# UpperPlumbingBayBoardSchematic.net
KiCad netlist of a schematic drawn in Altium Designer
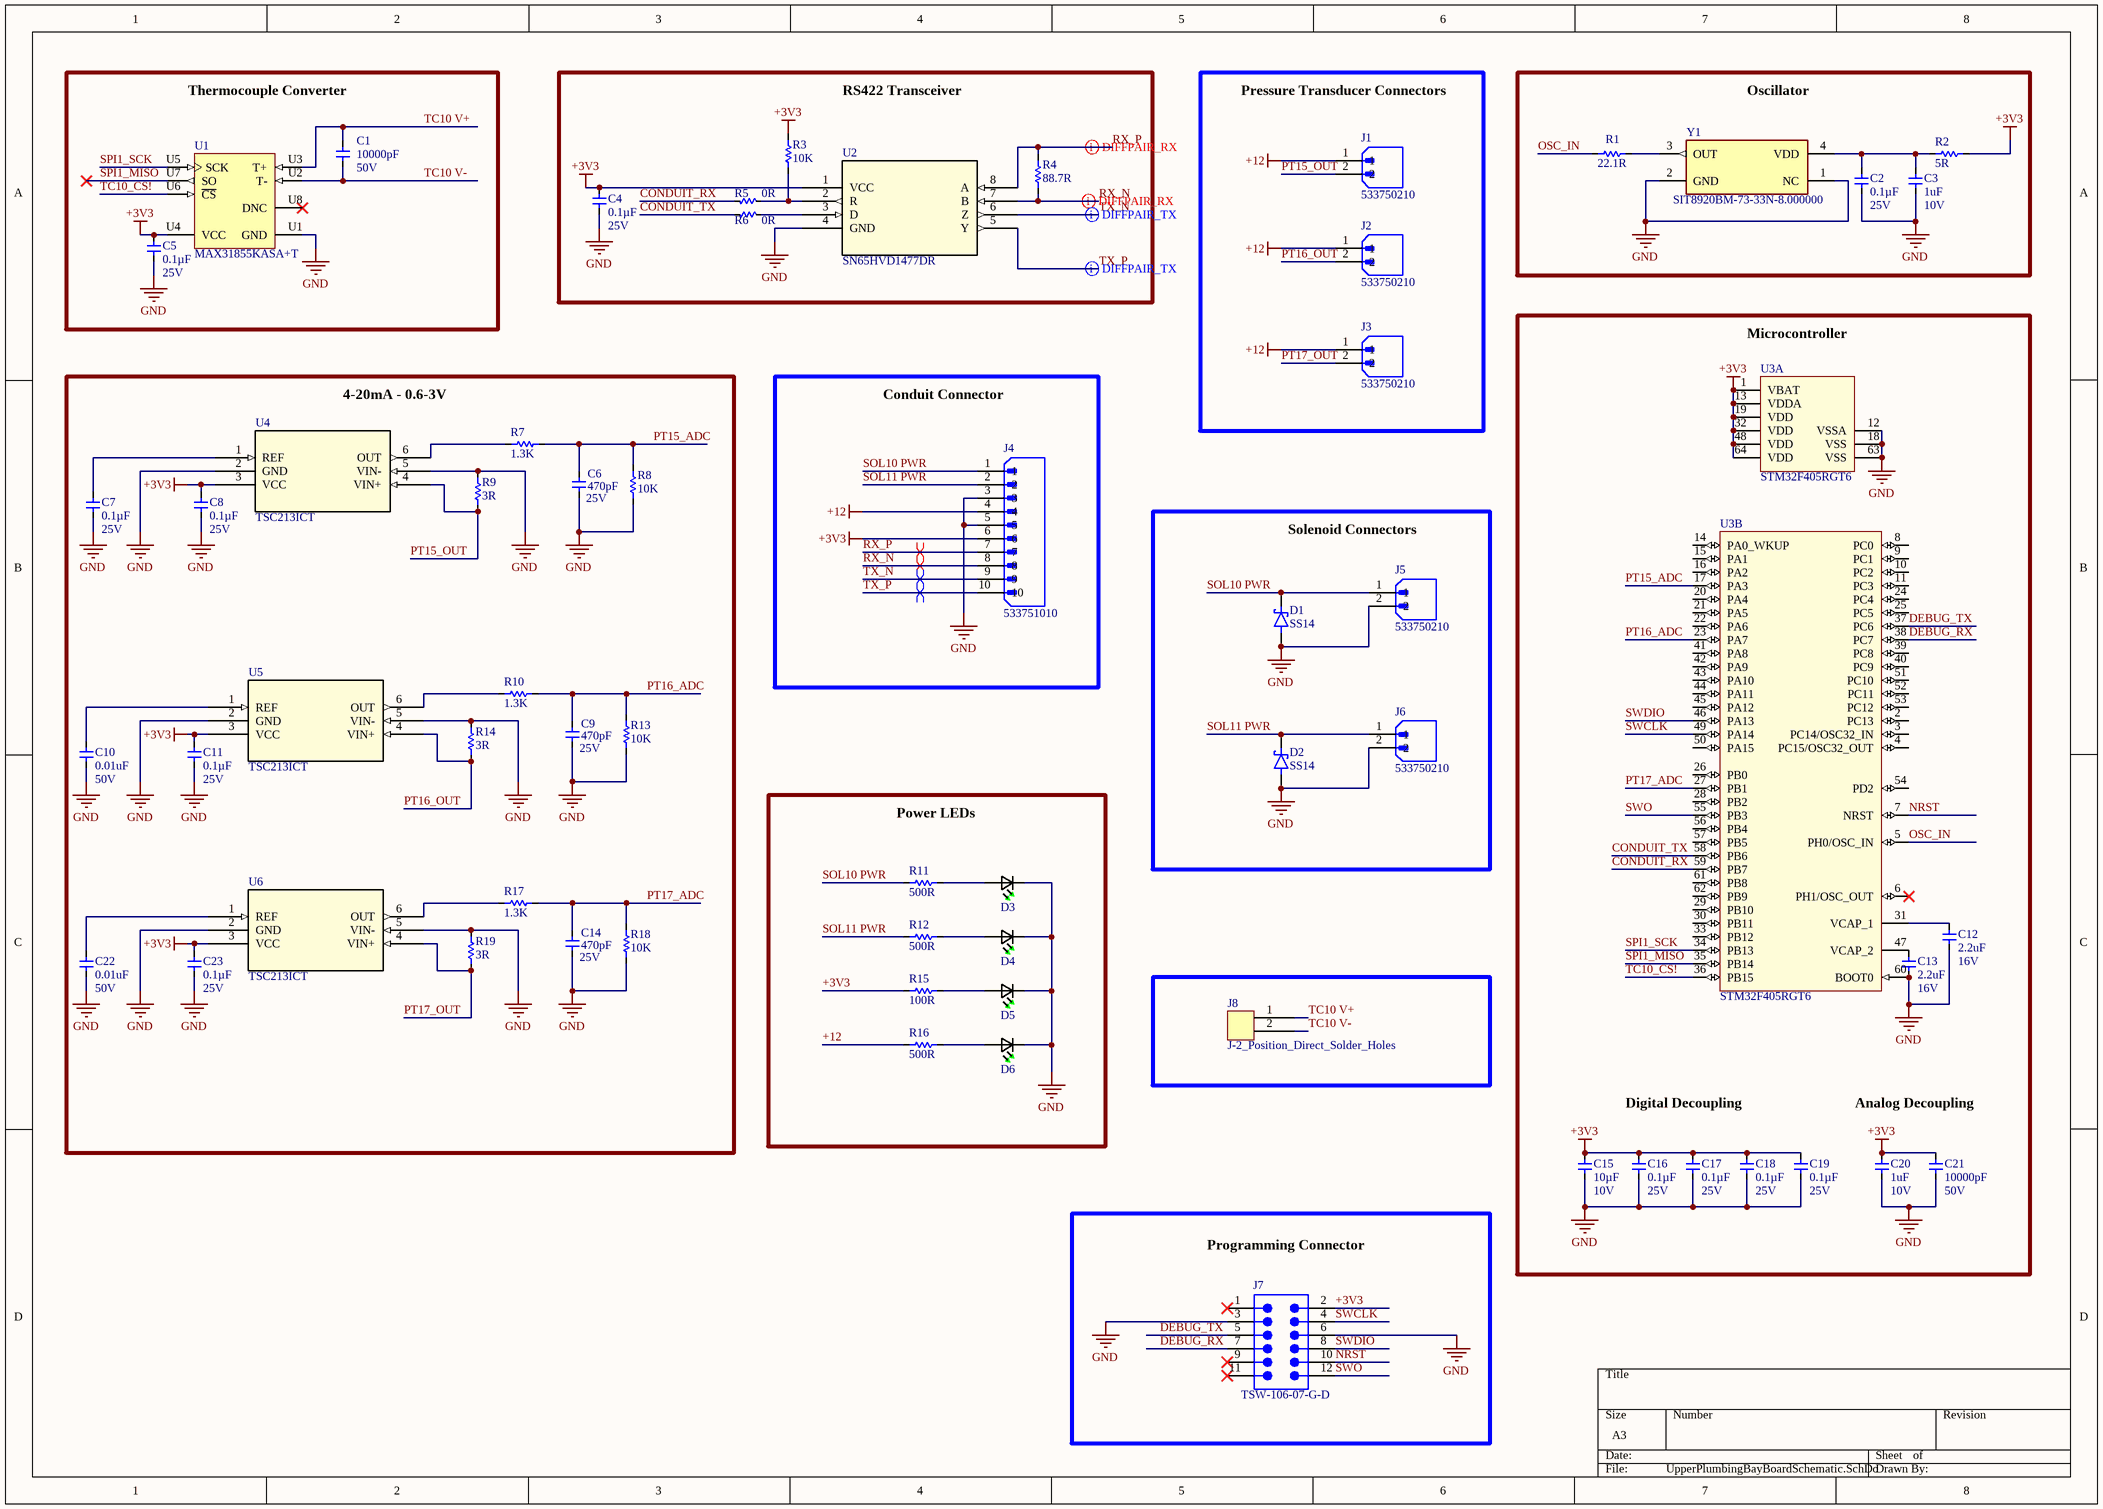
[diagram p0: UpperPlumbingBayBoardSchematic.SchDoc]

(export (version "E")
  (design (tool "Eeschema 10.0.6"))
  (components
    (comp (ref "C1")
      (value "CGA3E2X7R1H103K080AA")
      (footprint "0603")
      (description "CAP CER 10000PF 50V X7R 0603")
      (fields
        (field (name "MANUFACTURER") "TDK Corporation")
        (field (name "TOLERANCE") "±10%")
        (field (name "CAPACITANCE") "10000pF")
        (field (name "VOLTAGE - RATED") "50V")
      )
      (libsource (lib "BioRocketSchematics") (part "CGA3E2X7R1H103K080AA"))
    )
    (comp (ref "C2")
      (value "CGA3E2X7R1E104K080AA")
      (footprint "0603")
      (description "CAP CER 0.1UF 25V X7R 0603")
      (fields
        (field (name "MANUFACTURER") "TDK Corporation")
        (field (name "TOLERANCE") "±10%")
        (field (name "CAPACITANCE") "0.1µF")
        (field (name "VOLTAGE - RATED") "25V")
      )
      (libsource (lib "") (part "CGA3E2X7R1E104K080AA_1"))
    )
    (comp (ref "C3")
      (value "CL10A105KP8NNNC")
      (footprint "0603")
      (description "CAP CER 1UF 10V X5R 0603")
      (fields
        (field (name "MANUFACTURER") "Samsung Electro-Mechanics")
        (field (name "TOLERANCE") "±10%")
        (field (name "CAPACITANCE") "1uF")
        (field (name "VOLTAGE - RATED") "10V")
      )
      (libsource (lib "") (part "CL10A105KP8NNNC_1"))
    )
    (comp (ref "C4")
      (value "CGA3E2X7R1E104K080AA")
      (footprint "0603")
      (description "CAP CER 0.1UF 25V X7R 0603")
      (fields
        (field (name "MANUFACTURER") "TDK Corporation")
        (field (name "TOLERANCE") "±10%")
        (field (name "CAPACITANCE") "0.1µF")
        (field (name "VOLTAGE - RATED") "25V")
      )
      (libsource (lib "BioRocketSchematics") (part "CGA3E2X7R1E104K080AA"))
    )
    (comp (ref "C5")
      (value "CGA3E2X7R1E104K080AA")
      (footprint "0603")
      (description "CAP CER 0.1UF 25V X7R 0603")
      (fields
        (field (name "MANUFACTURER") "TDK Corporation")
        (field (name "TOLERANCE") "±10%")
        (field (name "CAPACITANCE") "0.1µF")
        (field (name "VOLTAGE - RATED") "25V")
      )
      (libsource (lib "BioRocketSchematics") (part "CGA3E2X7R1E104K080AA"))
    )
    (comp (ref "C6")
      (value "06031C471JAZ2A")
      (footprint "0603")
      (description "Multilayer Ceramic Capacitors MLCC - SMD/SMT 100V 470pF X7R 0603 5% Flex Soft")
      (fields
        (field (name "MANUFACTURER") "TDK Corporation")
        (field (name "TOLERANCE") "±10%")
        (field (name "CAPACITANCE") "470pF")
        (field (name "VOLTAGE - RATED") "25V")
      )
      (libsource (lib "BioRocketSchematics") (part "CGA3E2X7R1E104K080AA"))
    )
    (comp (ref "C7")
      (value "06035A103JAT2A")
      (footprint "0603")
      (description "Multilayer Ceramic Capacitors MLCC - SMD/SMT .01UF 50V 5% 0603")
      (fields
        (field (name "MANUFACTURER") "TDK Corporation")
        (field (name "TOLERANCE") "±10%")
        (field (name "CAPACITANCE") "0.1µF")
        (field (name "VOLTAGE - RATED") "25V")
      )
      (libsource (lib "altium-import") (part "root_2_CGA3E2X7R1E104K080AA_"))
    )
    (comp (ref "C8")
      (value "CGA3E2X7R1E104K080AA")
      (footprint "0603")
      (description "CAP CER 0.1UF 25V X7R 0603")
      (fields
        (field (name "MANUFACTURER") "TDK Corporation")
        (field (name "TOLERANCE") "±10%")
        (field (name "CAPACITANCE") "0.1µF")
        (field (name "VOLTAGE - RATED") "25V")
      )
      (libsource (lib "BioRocketSchematics") (part "CGA3E2X7R1E104K080AA"))
    )
    (comp (ref "C9")
      (value "06031C471JAZ2A")
      (footprint "0603")
      (description "Multilayer Ceramic Capacitors MLCC - SMD/SMT 100V 470pF X7R 0603 5% Flex Soft")
      (fields
        (field (name "MANUFACTURER") "TDK Corporation")
        (field (name "TOLERANCE") "±10%")
        (field (name "CAPACITANCE") "470pF")
        (field (name "VOLTAGE - RATED") "25V")
      )
      (libsource (lib "BioRocketSchematics") (part "CGA3E2X7R1E104K080AA"))
    )
    (comp (ref "C10")
      (value "06035A103JAT2A")
      (footprint "0603")
      (description "Multilayer Ceramic Capacitors MLCC - SMD/SMT .01UF 50V 5% 0603")
      (fields
        (field (name "MANUFACTURER") "TDK Corporation")
        (field (name "TOLERANCE") "±10%")
        (field (name "CAPACITANCE") "0.01uF")
        (field (name "VOLTAGE - RATED") "50V")
      )
      (libsource (lib "altium-import") (part "root_2_CGA3E2X7R1E104K080AA_"))
    )
    (comp (ref "C11")
      (value "CGA3E2X7R1E104K080AA")
      (footprint "0603")
      (description "CAP CER 0.1UF 25V X7R 0603")
      (fields
        (field (name "MANUFACTURER") "TDK Corporation")
        (field (name "TOLERANCE") "±10%")
        (field (name "CAPACITANCE") "0.1µF")
        (field (name "VOLTAGE - RATED") "25V")
      )
      (libsource (lib "BioRocketSchematics") (part "CGA3E2X7R1E104K080AA"))
    )
    (comp (ref "C12")
      (value "C1608X5R1C225K080AB")
      (footprint "0603")
      (description "CAP CER 2.2UF 16V X5R 0603")
      (fields
        (field (name "MANUFACTURER") "TDK Corporation")
        (field (name "TOLERANCE") "±10%")
        (field (name "CAPACITANCE") "2.2uF")
        (field (name "VOLTAGE - RATED") "16V")
      )
      (libsource (lib "BioRocketSchematics") (part "C1608X5R1C225K080AB"))
    )
    (comp (ref "C13")
      (value "C1608X5R1C225K080AB")
      (footprint "0603")
      (description "CAP CER 2.2UF 16V X5R 0603")
      (fields
        (field (name "MANUFACTURER") "TDK Corporation")
        (field (name "TOLERANCE") "±10%")
        (field (name "CAPACITANCE") "2.2uF")
        (field (name "VOLTAGE - RATED") "16V")
      )
      (libsource (lib "BioRocketSchematics") (part "C1608X5R1C225K080AB"))
    )
    (comp (ref "C14")
      (value "06031C471JAZ2A")
      (footprint "0603")
      (description "Multilayer Ceramic Capacitors MLCC - SMD/SMT 100V 470pF X7R 0603 5% Flex Soft")
      (fields
        (field (name "MANUFACTURER") "TDK Corporation")
        (field (name "TOLERANCE") "±10%")
        (field (name "CAPACITANCE") "470pF")
        (field (name "VOLTAGE - RATED") "25V")
      )
      (libsource (lib "BioRocketSchematics") (part "CGA3E2X7R1E104K080AA"))
    )
    (comp (ref "C15")
      (value "CGA3EDX7T1A106M080AU")
      (footprint "0603")
      (description "Multilayer Ceramic Capacitors MLCC - SMD/SMT 0603,X7T,10V,10uF,+/-20%,0.8mm, AEC-Q200")
      (fields
        (field (name "MANUFACTURER") "Samsung Electro-Mechanics")
        (field (name "TOLERANCE") "±20%")
        (field (name "CAPACITANCE") "10µF")
        (field (name "VOLTAGE - RATED") "10V")
      )
      (libsource (lib "BioRocketSchematics") (part "CL10A106MP8NNNC"))
    )
    (comp (ref "C16")
      (value "CGA3E2X7R1E104K080AA")
      (footprint "0603")
      (description "CAP CER 0.1UF 25V X7R 0603")
      (fields
        (field (name "MANUFACTURER") "TDK Corporation")
        (field (name "TOLERANCE") "±10%")
        (field (name "CAPACITANCE") "0.1µF")
        (field (name "VOLTAGE - RATED") "25V")
      )
      (libsource (lib "BioRocketSchematics") (part "CGA3E2X7R1E104K080AA"))
    )
    (comp (ref "C17")
      (value "CGA3E2X7R1E104K080AA")
      (footprint "0603")
      (description "CAP CER 0.1UF 25V X7R 0603")
      (fields
        (field (name "MANUFACTURER") "TDK Corporation")
        (field (name "TOLERANCE") "±10%")
        (field (name "CAPACITANCE") "0.1µF")
        (field (name "VOLTAGE - RATED") "25V")
      )
      (libsource (lib "BioRocketSchematics") (part "CGA3E2X7R1E104K080AA"))
    )
    (comp (ref "C18")
      (value "CGA3E2X7R1E104K080AA")
      (footprint "0603")
      (description "CAP CER 0.1UF 25V X7R 0603")
      (fields
        (field (name "MANUFACTURER") "TDK Corporation")
        (field (name "TOLERANCE") "±10%")
        (field (name "CAPACITANCE") "0.1µF")
        (field (name "VOLTAGE - RATED") "25V")
      )
      (libsource (lib "BioRocketSchematics") (part "CGA3E2X7R1E104K080AA"))
    )
    (comp (ref "C19")
      (value "CGA3E2X7R1E104K080AA")
      (footprint "0603")
      (description "CAP CER 0.1UF 25V X7R 0603")
      (fields
        (field (name "MANUFACTURER") "TDK Corporation")
        (field (name "TOLERANCE") "±10%")
        (field (name "CAPACITANCE") "0.1µF")
        (field (name "VOLTAGE - RATED") "25V")
      )
      (libsource (lib "BioRocketSchematics") (part "CGA3E2X7R1E104K080AA"))
    )
    (comp (ref "C20")
      (value "CL10A105KP8NNNC")
      (footprint "0603")
      (description "CAP CER 1UF 10V X5R 0603")
      (fields
        (field (name "MANUFACTURER") "Samsung Electro-Mechanics")
        (field (name "TOLERANCE") "±10%")
        (field (name "CAPACITANCE") "1uF")
        (field (name "VOLTAGE - RATED") "10V")
      )
      (libsource (lib "BioRocketSchematics") (part "CL10A105KP8NNNC"))
    )
    (comp (ref "C21")
      (value "CGA3E2X7R1H103K080AA")
      (footprint "0603")
      (description "CAP CER 10000PF 50V X7R 0603")
      (fields
        (field (name "MANUFACTURER") "TDK Corporation")
        (field (name "TOLERANCE") "±10%")
        (field (name "CAPACITANCE") "10000pF")
        (field (name "VOLTAGE - RATED") "50V")
      )
      (libsource (lib "BioRocketSchematics") (part "CGA3E2X7R1H103K080AA"))
    )
    (comp (ref "C22")
      (value "06035A103JAT2A")
      (footprint "0603")
      (description "Multilayer Ceramic Capacitors MLCC - SMD/SMT .01UF 50V 5% 0603")
      (fields
        (field (name "MANUFACTURER") "TDK Corporation")
        (field (name "TOLERANCE") "±10%")
        (field (name "CAPACITANCE") "0.01uF")
        (field (name "VOLTAGE - RATED") "50V")
      )
      (libsource (lib "altium-import") (part "root_2_CGA3E2X7R1E104K080AA_"))
    )
    (comp (ref "C23")
      (value "CGA3E2X7R1E104K080AA")
      (footprint "0603")
      (description "CAP CER 0.1UF 25V X7R 0603")
      (fields
        (field (name "MANUFACTURER") "TDK Corporation")
        (field (name "TOLERANCE") "±10%")
        (field (name "CAPACITANCE") "0.1µF")
        (field (name "VOLTAGE - RATED") "25V")
      )
      (libsource (lib "BioRocketSchematics") (part "CGA3E2X7R1E104K080AA"))
    )
    (comp (ref "D1")
      (value "SS14")
      (footprint "DIOM4325X250N")
      (description "Schottky Diodes & Rectifiers SMA 40V 1.0A")
      (libsource (lib "BioRocketSchematics") (part "SS14"))
    )
    (comp (ref "D2")
      (value "SS14")
      (footprint "DIOM4325X250N")
      (description "Schottky Diodes & Rectifiers SMA 40V 1.0A")
      (libsource (lib "BioRocketSchematics") (part "SS14"))
    )
    (comp (ref "D3")
      (value "LTST-C191KGKT")
      (footprint "LTST-C191KGKT")
      (description "LED,  LTST-C191KGKT")
      (fields (field (name "MANUFACTURER") "Vishay Lite-On"))
      (libsource (lib "BioRocketSchematics") (part "LTST-C191KGKT"))
    )
    (comp (ref "D4")
      (value "LTST-C191KGKT")
      (footprint "LTST-C191KGKT")
      (description "LED,  LTST-C191KGKT")
      (fields (field (name "MANUFACTURER") "Vishay Lite-On"))
      (libsource (lib "BioRocketSchematics") (part "LTST-C191KGKT"))
    )
    (comp (ref "D5")
      (value "LTST-C191KGKT")
      (footprint "LTST-C191KGKT")
      (description "LED,  LTST-C191KGKT")
      (fields (field (name "MANUFACTURER") "Vishay Lite-On"))
      (libsource (lib "BioRocketSchematics") (part "LTST-C191KGKT"))
    )
    (comp (ref "D6")
      (value "LTST-C191KGKT")
      (footprint "LTST-C191KGKT")
      (description "LED,  LTST-C191KGKT")
      (fields (field (name "MANUFACTURER") "Vishay Lite-On"))
      (libsource (lib "BioRocketSchematics") (part "LTST-C191KGKT"))
    )
    (comp (ref "J1")
      (value "533750210")
      (footprint "MOLEX_533750210")
      (libsource (lib "BioRocketSchematics") (part "533750210"))
    )
    (comp (ref "J2")
      (value "533750210")
      (footprint "MOLEX_533750210")
      (libsource (lib "BioRocketSchematics") (part "533750210"))
    )
    (comp (ref "J3")
      (value "533750210")
      (footprint "MOLEX_533750210")
      (libsource (lib "BioRocketSchematics") (part "533750210"))
    )
    (comp (ref "J4")
      (value "533751010")
      (footprint "MOLEX_533751010")
      (libsource (lib "BioRocketSchematics") (part "533751010"))
    )
    (comp (ref "J5")
      (value "533750210")
      (footprint "MOLEX_533750210")
      (libsource (lib "BioRocketSchematics") (part "533750210"))
    )
    (comp (ref "J6")
      (value "533750210")
      (footprint "MOLEX_533750210")
      (libsource (lib "BioRocketSchematics") (part "533750210"))
    )
    (comp (ref "J7")
      (value "TSW-106-07-G-D")
      (footprint "SMTC-TSW-106-07-X-D")
      (description "0.025\" SQ Post Header, Through-hole, Vertical, -55 to 125 degC, 2.54 mm Pitch, 12-Pin, Male, RoHS")
      (fields (field (name "MANUFACTURER") "Samtec"))
      (libsource (lib "BioRocketSchematics") (part "SMTC-TSW-106-07-X-D_1"))
    )
    (comp (ref "J8")
      (value "J-2_Position_Direct_Solder_Holes")
      (footprint "J-2_Position_Direct_Solder_Holes")
      (libsource (lib "PlumBay_SchLib") (part "J-2_Position_Direct_Solder_Holes"))
    )
    (comp (ref "R1")
      (value "ERJ-P03F22R1V")
      (footprint "0603")
      (description "Thick Film Resistors - SMD 0603 22.1ohms 0.2W 1% AEC-Q200")
      (fields
        (field (name "MANUFACTURER") "Panasonic")
        (field (name "MANUFACTURER PART NUMBER") "ERJ-3EKF38R3V")
        (field (name "RESISTANCE") "22.1R")
      )
      (libsource (lib "BioRocketSchematics") (part "ERJ-3EKF38R3V"))
    )
    (comp (ref "R2")
      (value "PWR2010W5R00JE")
      (footprint "BO_PWR2010")
      (description "Res Wirewound 2010 5 Ohm 5% 1/2W ±50ppm/°C Molded SMD SMD T/R")
      (fields
        (field (name "MANUFACTURER") "Bourns")
        (field (name "TOLERANCE") "5%")
        (field (name "RESISTANCE") "5R")
      )
      (libsource (lib "BioRocketSchematics") (part "PWR2010W5R00JE"))
    )
    (comp (ref "R3")
      (value "ERJ-3GEYJ103V")
      (footprint "0603")
      (description "SMD Chip Resistor, 10 kOhm, ï¿½ 5%, 100 mW, 0603 [1608 Metric], Thick Film, General Purpose")
      (fields
        (field (name "TOLERANCE") "±5%")
        (field (name "MANUFACTURER") "Panasonic Electronic Components")
        (field (name "RESISTANCE") "10K")
      )
      (libsource (lib "BioRocketSchematics") (part "ERJ-3GEYJ103V"))
    )
    (comp (ref "R4")
      (value "RC0201FR-0788R7L")
      (footprint "0603")
      (description "Thick Film Resistors - SMD 88.7Ohms 1/20W 0201 1%")
      (fields
        (field (name "TOLERANCE") "±5%")
        (field (name "MANUFACTURER") "Panasonic Electronic Components")
        (field (name "RESISTANCE") "88.7R")
      )
      (libsource (lib "BioRocketSchematics") (part "ERJ-3GEYJ103V"))
    )
    (comp (ref "R5")
      (value "0R")
      (footprint "0603")
      (description "RES SMD 0 OHM 1% JUMPER 1/10W 0603")
      (fields
        (field (name "DISTRIBUTOR PART #") "RMCF0603ZT0R00CT-ND")
        (field (name "MANUFACTURER") "Stackpole Electronics Inc")
      )
      (libsource (lib "BioRocketSchematics") (part "RT-0R00-F-1/10W-0603"))
    )
    (comp (ref "R6")
      (value "0R")
      (footprint "0603")
      (description "RES SMD 0 OHM 1% JUMPER 1/10W 0603")
      (fields
        (field (name "DISTRIBUTOR PART #") "RMCF0603ZT0R00CT-ND")
        (field (name "MANUFACTURER") "Stackpole Electronics Inc")
      )
      (libsource (lib "BioRocketSchematics") (part "RT-0R00-F-1/10W-0603"))
    )
    (comp (ref "R7")
      (value "ERJ-H3EF1301V")
      (footprint "0603")
      (description "Thick Film Resistors - SMD 0603 1.3KOhm 1% AEC-Q200")
      (fields
        (field (name "MANUFACTURER") "Bourns")
        (field (name "MANUFACTURER PART NUMBER") "PWR2010W5R00JE")
        (field (name "RESISTANCE") "1.3K")
      )
      (libsource (lib "BioRocketSchematics") (part "PWR2010W5R00JE"))
    )
    (comp (ref "R8")
      (value "ERJ-3GEYJ103V")
      (footprint "0603")
      (description "SMD Chip Resistor, 10 kOhm, ï¿½ 5%, 100 mW, 0603 [1608 Metric], Thick Film, General Purpose")
      (fields
        (field (name "TOLERANCE") "±5%")
        (field (name "MANUFACTURER") "Panasonic Electronic Components")
        (field (name "RESISTANCE") "10K")
      )
      (libsource (lib "BioRocketSchematics") (part "ERJ-3GEYJ103V"))
    )
    (comp (ref "R9")
      (value "ERJ-3RQF3R0V")
      (footprint "0603")
      (description "Current Sense Resistors - SMD 0603 3.0ohm 1% Curr Sense AEC-Q200")
      (fields
        (field (name "TOLERANCE") "±5%")
        (field (name "MANUFACTURER") "Panasonic Electronic Components")
        (field (name "RESISTANCE") "3R")
      )
      (libsource (lib "BioRocketSchematics") (part "ERJ-3GEYJ103V"))
    )
    (comp (ref "R10")
      (value "ERJ-H3EF1301V")
      (footprint "0603")
      (description "Thick Film Resistors - SMD 0603 1.3KOhm 1% AEC-Q200")
      (fields
        (field (name "MANUFACTURER") "Bourns")
        (field (name "MANUFACTURER PART NUMBER") "PWR2010W5R00JE")
        (field (name "RESISTANCE") "1.3K")
      )
      (libsource (lib "BioRocketSchematics") (part "PWR2010W5R00JE"))
    )
    (comp (ref "R11")
      (value "RT0603BRC07500RL")
      (footprint "0603")
      (description "Thin Film Resistors - SMD 500 ohm 0.1% 15ppm H igh Stability")
      (fields
        (field (name "MANUFACTURER") "Yageo")
        (field (name "MANUFACTURER PART NUMBER") "RC0603FR-071KL")
        (field (name "RESISTANCE") "500R")
      )
      (libsource (lib "BioRocketSchematics") (part "RC0603FR-071KL"))
    )
    (comp (ref "R12")
      (value "RT0603BRC07500RL")
      (footprint "0603")
      (description "Thin Film Resistors - SMD 500 ohm 0.1% 15ppm H igh Stability")
      (fields
        (field (name "MANUFACTURER") "Yageo")
        (field (name "MANUFACTURER PART NUMBER") "RC0603FR-071KL")
        (field (name "RESISTANCE") "500R")
      )
      (libsource (lib "BioRocketSchematics") (part "RC0603FR-071KL"))
    )
    (comp (ref "R13")
      (value "ERJ-3GEYJ103V")
      (footprint "0603")
      (description "SMD Chip Resistor, 10 kOhm, ï¿½ 5%, 100 mW, 0603 [1608 Metric], Thick Film, General Purpose")
      (fields
        (field (name "TOLERANCE") "±5%")
        (field (name "MANUFACTURER") "Panasonic Electronic Components")
        (field (name "RESISTANCE") "10K")
      )
      (libsource (lib "BioRocketSchematics") (part "ERJ-3GEYJ103V"))
    )
    (comp (ref "R14")
      (value "ERJ-3RQF3R0V")
      (footprint "0603")
      (description "Current Sense Resistors - SMD 0603 3.0ohm 1% Curr Sense AEC-Q200")
      (fields
        (field (name "TOLERANCE") "±5%")
        (field (name "MANUFACTURER") "Panasonic Electronic Components")
        (field (name "RESISTANCE") "3R")
      )
      (libsource (lib "BioRocketSchematics") (part "ERJ-3GEYJ103V"))
    )
    (comp (ref "R15")
      (value "ERJ-P03F1000V")
      (footprint "0603")
      (description "Thick Film Resistors - SMD 0603 100ohms 0.2W 1% AEC-Q200")
      (fields
        (field (name "MANUFACTURER") "TE Connectivity")
        (field (name "MANUFACTURER PART NUMBER") "CRGCQ0402J330R")
        (field (name "RESISTANCE") "100R")
      )
      (libsource (lib "BioRocketSchematics") (part "CRGCQ0402J330R"))
    )
    (comp (ref "R16")
      (value "RT0603BRC07500RL")
      (footprint "0603")
      (description "Thin Film Resistors - SMD 500 ohm 0.1% 15ppm H igh Stability")
      (fields
        (field (name "MANUFACTURER") "Yageo")
        (field (name "MANUFACTURER PART NUMBER") "RC0603FR-071KL")
        (field (name "RESISTANCE") "500R")
      )
      (libsource (lib "BioRocketSchematics") (part "RC0603FR-071KL"))
    )
    (comp (ref "R17")
      (value "ERJ-H3EF1301V")
      (footprint "0603")
      (description "Thick Film Resistors - SMD 0603 1.3KOhm 1% AEC-Q200")
      (fields
        (field (name "MANUFACTURER") "Bourns")
        (field (name "MANUFACTURER PART NUMBER") "PWR2010W5R00JE")
        (field (name "RESISTANCE") "1.3K")
      )
      (libsource (lib "BioRocketSchematics") (part "PWR2010W5R00JE"))
    )
    (comp (ref "R18")
      (value "ERJ-3GEYJ103V")
      (footprint "0603")
      (description "SMD Chip Resistor, 10 kOhm, ï¿½ 5%, 100 mW, 0603 [1608 Metric], Thick Film, General Purpose")
      (fields
        (field (name "TOLERANCE") "±5%")
        (field (name "MANUFACTURER") "Panasonic Electronic Components")
        (field (name "RESISTANCE") "10K")
      )
      (libsource (lib "BioRocketSchematics") (part "ERJ-3GEYJ103V"))
    )
    (comp (ref "R19")
      (value "ERJ-3RQF3R0V")
      (footprint "0603")
      (description "Current Sense Resistors - SMD 0603 3.0ohm 1% Curr Sense AEC-Q200")
      (fields
        (field (name "TOLERANCE") "±5%")
        (field (name "MANUFACTURER") "Panasonic Electronic Components")
        (field (name "RESISTANCE") "3R")
      )
      (libsource (lib "BioRocketSchematics") (part "ERJ-3GEYJ103V"))
    )
    (comp (ref "U1")
      (value "MAX31855KASA+T")
      (footprint "MAXM-S8+4_L")
      (fields (field (name "GENERIC PART NUMBER") "MAX31855"))
      (libsource (lib "BioRocketSchematics") (part "MAX31855-S8+4_1"))
    )
    (comp (ref "U2")
      (value "SN65HVD1477DR")
      (footprint "D8_TEX")
      (description "3.3V, Full-Duplex RS-485, 16kV IEC ESD, 50Mbps data rate, No Enables 8-SOIC -40 to 125")
      (fields (field (name "COPYRIGHT") "Copyright (C) 2022 Ultra Librarian. All rights reserved."))
      (libsource (lib "BioRocketSchematics") (part "SN65HVD1477DR"))
    )
    (comp (ref "U3")
      (value "STM32F405RGT6")
      (footprint "STM-LQFP64_L")
      (description "IC MCU 32BIT 1MB FLASH 64LQFP")
      (fields (field (name "MANUFACTURER") "STMicroelectronics"))
      (libsource (lib "BioRocketSchematics") (part "STM32F405RGT6"))
    )
    (comp (ref "U4")
      (value "TSC213ICT")
      (footprint "SC70-6_STM")
      (description "No Description Available")
      (libsource (lib "BioRocketSchematics") (part "TSC213ICT"))
    )
    (comp (ref "U5")
      (value "TSC213ICT")
      (footprint "SC70-6_STM")
      (description "No Description Available")
      (libsource (lib "BioRocketSchematics") (part "TSC213ICT"))
    )
    (comp (ref "U6")
      (value "TSC213ICT")
      (footprint "SC70-6_STM")
      (description "No Description Available")
      (libsource (lib "BioRocketSchematics") (part "TSC213ICT"))
    )
    (comp (ref "Y1")
      (value "SIT8920BM-73-33N-8.000000")
      (footprint "FP-SIT8920BM-73-33N-8_000-MFG")
      (description "MEMS OSC XO 8.0000MHZ LVCM LVTTL")
      (libsource (lib "Altium Content Vault") (part "f8eed742da43ac8d7009b5f8d825914"))
    )
  )
  (nets
    (net (code "1") (name "+3V3") (class "Default")
      (node (ref "C11") (pin "1") (pinfunction "1_1") (pintype "passive"))
      (node (ref "C15") (pin "1") (pinfunction "1_1") (pintype "passive"))
      (node (ref "C16") (pin "1") (pinfunction "1_1") (pintype "passive"))
      (node (ref "C17") (pin "1") (pinfunction "1_1") (pintype "passive"))
      (node (ref "C18") (pin "1") (pinfunction "1_1") (pintype "passive"))
      (node (ref "C19") (pin "1") (pinfunction "1_1") (pintype "passive"))
      (node (ref "C20") (pin "1") (pinfunction "1_1") (pintype "passive"))
      (node (ref "C21") (pin "1") (pinfunction "1_1") (pintype "passive"))
      (node (ref "C23") (pin "1") (pinfunction "1_1") (pintype "passive"))
      (node (ref "C4") (pin "1") (pinfunction "1_1") (pintype "passive"))
      (node (ref "C5") (pin "1") (pinfunction "1_1") (pintype "passive"))
      (node (ref "C8") (pin "1") (pinfunction "1_1") (pintype "passive"))
      (node (ref "J4") (pin "6") (pinfunction "6_6") (pintype "passive"))
      (node (ref "J7") (pin "2") (pinfunction "2_2") (pintype "passive"))
      (node (ref "R15") (pin "1") (pinfunction "1_1") (pintype "passive"))
      (node (ref "R2") (pin "2") (pinfunction "2_2") (pintype "passive"))
      (node (ref "R3") (pin "2") (pinfunction "2_2") (pintype "passive"))
      (node (ref "U1") (pin "U4") (pinfunction "VCC_U4") (pintype "power_in"))
      (node (ref "U2") (pin "1") (pinfunction "VCC_1") (pintype "power_in"))
      (node (ref "U3") (pin "1") (pinfunction "VBAT_1") (pintype "power_in"))
      (node (ref "U3") (pin "13") (pinfunction "VDDA_13") (pintype "power_in"))
      (node (ref "U3") (pin "19") (pinfunction "VDD_19") (pintype "power_in"))
      (node (ref "U3") (pin "32") (pinfunction "VDD_32") (pintype "power_in"))
      (node (ref "U3") (pin "48") (pinfunction "VDD_48") (pintype "power_in"))
      (node (ref "U3") (pin "64") (pinfunction "VDD_64") (pintype "power_in"))
      (node (ref "U4") (pin "3") (pinfunction "VCC_3") (pintype "power_in"))
      (node (ref "U5") (pin "3") (pinfunction "VCC_3") (pintype "power_in"))
      (node (ref "U6") (pin "3") (pinfunction "VCC_3") (pintype "power_in"))
    )
    (net (code "2") (name "+12") (class "Default")
      (node (ref "J1") (pin "1") (pinfunction "1_1") (pintype "passive"))
      (node (ref "J2") (pin "1") (pinfunction "1_1") (pintype "passive"))
      (node (ref "J3") (pin "1") (pinfunction "1_1") (pintype "passive"))
      (node (ref "J4") (pin "4") (pinfunction "4_4") (pintype "passive"))
      (node (ref "R16") (pin "1") (pinfunction "1_1") (pintype "passive"))
    )
    (net (code "3") (name "/CONDUIT_RX") (class "Default")
      (node (ref "R5") (pin "1") (pintype "passive"))
      (node (ref "U3") (pin "59") (pinfunction "PB7_59") (pintype "bidirectional"))
    )
    (net (code "4") (name "/CONDUIT_TX") (class "Default")
      (node (ref "R6") (pin "1") (pintype "passive"))
      (node (ref "U3") (pin "58") (pinfunction "PB6_58") (pintype "bidirectional"))
    )
    (net (code "5") (name "/DEBUG_RX") (class "Default")
      (node (ref "J7") (pin "7") (pinfunction "7_7") (pintype "passive"))
      (node (ref "U3") (pin "38") (pinfunction "PC7_38") (pintype "bidirectional"))
    )
    (net (code "6") (name "/DEBUG_TX") (class "Default")
      (node (ref "J7") (pin "5") (pinfunction "5_5") (pintype "passive"))
      (node (ref "U3") (pin "37") (pinfunction "PC6_37") (pintype "bidirectional"))
    )
    (net (code "7") (name "/NRST") (class "Default")
      (node (ref "J7") (pin "10") (pinfunction "10_10") (pintype "passive"))
      (node (ref "U3") (pin "7") (pinfunction "NRST_7") (pintype "bidirectional"))
    )
    (net (code "8") (name "/OSC_IN") (class "Default")
      (node (ref "R1") (pin "1") (pinfunction "1_1") (pintype "passive"))
      (node (ref "U3") (pin "5") (pinfunction "PH0/OSC_IN_5") (pintype "bidirectional"))
    )
    (net (code "9") (name "/PT15_ADC") (class "Default")
      (node (ref "C6") (pin "1") (pinfunction "1_1") (pintype "passive"))
      (node (ref "R7") (pin "2") (pinfunction "2_2") (pintype "passive"))
      (node (ref "R8") (pin "2") (pinfunction "2_2") (pintype "passive"))
      (node (ref "U3") (pin "17") (pinfunction "PA3_17") (pintype "bidirectional"))
    )
    (net (code "10") (name "/PT15_OUT") (class "Default")
      (node (ref "J1") (pin "2") (pinfunction "2_2") (pintype "passive"))
      (node (ref "R9") (pin "1") (pinfunction "1_1") (pintype "passive"))
      (node (ref "U4") (pin "4") (pinfunction "VIN+_4") (pintype "input"))
    )
    (net (code "11") (name "/PT16_ADC") (class "Default")
      (node (ref "C9") (pin "1") (pinfunction "1_1") (pintype "passive"))
      (node (ref "R10") (pin "2") (pinfunction "2_2") (pintype "passive"))
      (node (ref "R13") (pin "2") (pinfunction "2_2") (pintype "passive"))
      (node (ref "U3") (pin "23") (pinfunction "PA7_23") (pintype "bidirectional"))
    )
    (net (code "12") (name "/PT16_OUT") (class "Default")
      (node (ref "J2") (pin "2") (pinfunction "2_2") (pintype "passive"))
      (node (ref "R14") (pin "1") (pinfunction "1_1") (pintype "passive"))
      (node (ref "U5") (pin "4") (pinfunction "VIN+_4") (pintype "input"))
    )
    (net (code "13") (name "/PT17_ADC") (class "Default")
      (node (ref "C14") (pin "1") (pinfunction "1_1") (pintype "passive"))
      (node (ref "R17") (pin "2") (pinfunction "2_2") (pintype "passive"))
      (node (ref "R18") (pin "2") (pinfunction "2_2") (pintype "passive"))
      (node (ref "U3") (pin "27") (pinfunction "PB1_27") (pintype "bidirectional"))
    )
    (net (code "14") (name "/PT17_OUT") (class "Default")
      (node (ref "J3") (pin "2") (pinfunction "2_2") (pintype "passive"))
      (node (ref "R19") (pin "1") (pinfunction "1_1") (pintype "passive"))
      (node (ref "U6") (pin "4") (pinfunction "VIN+_4") (pintype "input"))
    )
    (net (code "15") (name "/RX_N") (class "Default")
      (node (ref "J4") (pin "8") (pinfunction "8_8") (pintype "passive"))
      (node (ref "R4") (pin "1") (pinfunction "1_1") (pintype "passive"))
      (node (ref "U2") (pin "7") (pinfunction "B_7") (pintype "input"))
    )
    (net (code "16") (name "/RX_P") (class "Default")
      (node (ref "J4") (pin "7") (pinfunction "7_7") (pintype "passive"))
      (node (ref "R4") (pin "2") (pinfunction "2_2") (pintype "passive"))
      (node (ref "U2") (pin "8") (pinfunction "A_8") (pintype "input"))
    )
    (net (code "17") (name "/SOL10 PWR") (class "Default")
      (node (ref "D1") (pin "C") (pinfunction "K_C") (pintype "passive"))
      (node (ref "J4") (pin "1") (pinfunction "1_1") (pintype "passive"))
      (node (ref "J5") (pin "1") (pinfunction "1_1") (pintype "passive"))
      (node (ref "R11") (pin "1") (pinfunction "1_1") (pintype "passive"))
    )
    (net (code "18") (name "/SOL11 PWR") (class "Default")
      (node (ref "D2") (pin "C") (pinfunction "K_C") (pintype "passive"))
      (node (ref "J4") (pin "2") (pinfunction "2_2") (pintype "passive"))
      (node (ref "J6") (pin "1") (pinfunction "1_1") (pintype "passive"))
      (node (ref "R12") (pin "1") (pinfunction "1_1") (pintype "passive"))
    )
    (net (code "19") (name "/SPI1_MISO") (class "Default")
      (node (ref "U1") (pin "U7") (pinfunction "SO_U7") (pintype "output"))
      (node (ref "U3") (pin "35") (pinfunction "PB14_35") (pintype "bidirectional"))
    )
    (net (code "20") (name "/SPI1_SCK") (class "Default")
      (node (ref "U1") (pin "U5") (pinfunction "SCK_U5") (pintype "input"))
      (node (ref "U3") (pin "34") (pinfunction "PB13_34") (pintype "bidirectional"))
    )
    (net (code "21") (name "/SWCLK") (class "Default")
      (node (ref "J7") (pin "4") (pinfunction "4_4") (pintype "passive"))
      (node (ref "U3") (pin "49") (pinfunction "PA14_49") (pintype "bidirectional"))
    )
    (net (code "22") (name "/SWDIO") (class "Default")
      (node (ref "J7") (pin "8") (pinfunction "8_8") (pintype "passive"))
      (node (ref "U3") (pin "46") (pinfunction "PA13_46") (pintype "bidirectional"))
    )
    (net (code "23") (name "/SWO") (class "Default")
      (node (ref "J7") (pin "12") (pinfunction "12_12") (pintype "passive"))
      (node (ref "U3") (pin "55") (pinfunction "PB3_55") (pintype "bidirectional"))
    )
    (net (code "24") (name "/TC10 V+") (class "Default")
      (node (ref "C1") (pin "1") (pinfunction "1_1") (pintype "passive"))
      (node (ref "J8") (pin "1") (pintype "passive"))
      (node (ref "U1") (pin "U3") (pinfunction "T+_U3") (pintype "input"))
    )
    (net (code "25") (name "/TC10 V-") (class "Default")
      (node (ref "C1") (pin "2") (pinfunction "2_2") (pintype "passive"))
      (node (ref "J8") (pin "2") (pintype "passive"))
      (node (ref "U1") (pin "U2") (pinfunction "T-_U2") (pintype "input"))
    )
    (net (code "26") (name "/TC10_CS!") (class "Default")
      (node (ref "U1") (pin "U6") (pinfunction "~{CS}_U6") (pintype "input"))
      (node (ref "U3") (pin "36") (pinfunction "PB15_36") (pintype "bidirectional"))
    )
    (net (code "27") (name "/TX_N") (class "Default")
      (node (ref "J4") (pin "9") (pinfunction "9_9") (pintype "passive"))
      (node (ref "U2") (pin "6") (pinfunction "Z_6") (pintype "output"))
    )
    (net (code "28") (name "/TX_P") (class "Default")
      (node (ref "J4") (pin "10") (pinfunction "10_10") (pintype "passive"))
      (node (ref "U2") (pin "5") (pinfunction "Y_5") (pintype "output"))
    )
    (net (code "29") (name "GND") (class "Default")
      (node (ref "C10") (pin "2") (pinfunction "2_2") (pintype "passive"))
      (node (ref "C11") (pin "2") (pinfunction "2_2") (pintype "passive"))
      (node (ref "C12") (pin "1") (pinfunction "1_1") (pintype "passive"))
      (node (ref "C13") (pin "2") (pinfunction "2_2") (pintype "passive"))
      (node (ref "C14") (pin "2") (pinfunction "2_2") (pintype "passive"))
      (node (ref "C15") (pin "2") (pinfunction "2_2") (pintype "passive"))
      (node (ref "C16") (pin "2") (pinfunction "2_2") (pintype "passive"))
      (node (ref "C17") (pin "2") (pinfunction "2_2") (pintype "passive"))
      (node (ref "C18") (pin "2") (pinfunction "2_2") (pintype "passive"))
      (node (ref "C19") (pin "2") (pinfunction "2_2") (pintype "passive"))
      (node (ref "C2") (pin "1") (pinfunction "1_1") (pintype "passive"))
      (node (ref "C20") (pin "2") (pinfunction "2_2") (pintype "passive"))
      (node (ref "C21") (pin "2") (pinfunction "2_2") (pintype "passive"))
      (node (ref "C22") (pin "2") (pinfunction "2_2") (pintype "passive"))
      (node (ref "C23") (pin "2") (pinfunction "2_2") (pintype "passive"))
      (node (ref "C3") (pin "1") (pinfunction "1_1") (pintype "passive"))
      (node (ref "C4") (pin "2") (pinfunction "2_2") (pintype "passive"))
      (node (ref "C5") (pin "2") (pinfunction "2_2") (pintype "passive"))
      (node (ref "C6") (pin "2") (pinfunction "2_2") (pintype "passive"))
      (node (ref "C7") (pin "2") (pinfunction "2_2") (pintype "passive"))
      (node (ref "C8") (pin "2") (pinfunction "2_2") (pintype "passive"))
      (node (ref "C9") (pin "2") (pinfunction "2_2") (pintype "passive"))
      (node (ref "D1") (pin "A") (pinfunction "A_A") (pintype "passive"))
      (node (ref "D2") (pin "A") (pinfunction "A_A") (pintype "passive"))
      (node (ref "D3") (pin "1") (pinfunction "K2_1") (pintype "passive"))
      (node (ref "D4") (pin "1") (pinfunction "K2_1") (pintype "passive"))
      (node (ref "D5") (pin "1") (pinfunction "K2_1") (pintype "passive"))
      (node (ref "D6") (pin "1") (pinfunction "K2_1") (pintype "passive"))
      (node (ref "J4") (pin "3") (pinfunction "3_3") (pintype "passive"))
      (node (ref "J4") (pin "5") (pinfunction "5_5") (pintype "passive"))
      (node (ref "J5") (pin "2") (pinfunction "2_2") (pintype "passive"))
      (node (ref "J6") (pin "2") (pinfunction "2_2") (pintype "passive"))
      (node (ref "J7") (pin "3") (pinfunction "3_3") (pintype "passive"))
      (node (ref "J7") (pin "6") (pinfunction "6_6") (pintype "passive"))
      (node (ref "R13") (pin "1") (pinfunction "1_1") (pintype "passive"))
      (node (ref "R14") (pin "2") (pinfunction "2_2") (pintype "passive"))
      (node (ref "R18") (pin "1") (pinfunction "1_1") (pintype "passive"))
      (node (ref "R19") (pin "2") (pinfunction "2_2") (pintype "passive"))
      (node (ref "R8") (pin "1") (pinfunction "1_1") (pintype "passive"))
      (node (ref "R9") (pin "2") (pinfunction "2_2") (pintype "passive"))
      (node (ref "U1") (pin "U1") (pinfunction "GND_U1") (pintype "power_in"))
      (node (ref "U2") (pin "4") (pinfunction "GND_4") (pintype "power_in"))
      (node (ref "U3") (pin "12") (pinfunction "VSSA_12") (pintype "power_in"))
      (node (ref "U3") (pin "18") (pinfunction "VSS_18") (pintype "power_in"))
      (node (ref "U3") (pin "60") (pinfunction "BOOT0_60") (pintype "input"))
      (node (ref "U3") (pin "63") (pinfunction "VSS_63") (pintype "power_in"))
      (node (ref "U4") (pin "2") (pinfunction "GND_2") (pintype "power_in"))
      (node (ref "U4") (pin "5") (pinfunction "VIN-_5") (pintype "input"))
      (node (ref "U5") (pin "2") (pinfunction "GND_2") (pintype "power_in"))
      (node (ref "U5") (pin "5") (pinfunction "VIN-_5") (pintype "input"))
      (node (ref "U6") (pin "2") (pinfunction "GND_2") (pintype "power_in"))
      (node (ref "U6") (pin "5") (pinfunction "VIN-_5") (pintype "input"))
      (node (ref "Y1") (pin "1") (pinfunction "NC_1") (pintype "passive"))
      (node (ref "Y1") (pin "2") (pinfunction "GND_2") (pintype "power_in"))
    )
    (net (code "30") (name "Net-(D3-A2)") (class "Default")
      (node (ref "D3") (pin "2") (pinfunction "A2_2") (pintype "passive"))
      (node (ref "R11") (pin "2") (pinfunction "2_2") (pintype "passive"))
    )
    (net (code "31") (name "Net-(D4-A2)") (class "Default")
      (node (ref "D4") (pin "2") (pinfunction "A2_2") (pintype "passive"))
      (node (ref "R12") (pin "2") (pinfunction "2_2") (pintype "passive"))
    )
    (net (code "32") (name "Net-(D5-A2)") (class "Default")
      (node (ref "D5") (pin "2") (pinfunction "A2_2") (pintype "passive"))
      (node (ref "R15") (pin "2") (pinfunction "2_2") (pintype "passive"))
    )
    (net (code "33") (name "Net-(D6-A2)") (class "Default")
      (node (ref "D6") (pin "2") (pinfunction "A2_2") (pintype "passive"))
      (node (ref "R16") (pin "2") (pinfunction "2_2") (pintype "passive"))
    )
    (net (code "34") (name "Net-(U2-D)") (class "Default")
      (node (ref "R6") (pin "2") (pintype "passive"))
      (node (ref "U2") (pin "3") (pinfunction "D_3") (pintype "input"))
    )
    (net (code "35") (name "Net-(U2-R)") (class "Default")
      (node (ref "R3") (pin "1") (pinfunction "1_1") (pintype "passive"))
      (node (ref "R5") (pin "2") (pintype "passive"))
      (node (ref "U2") (pin "2") (pinfunction "R_2") (pintype "output"))
    )
    (net (code "36") (name "Net-(U3B-VCAP_1)") (class "Default")
      (node (ref "C12") (pin "2") (pinfunction "2_2") (pintype "passive"))
      (node (ref "U3") (pin "31") (pinfunction "VCAP_1_31") (pintype "power_in"))
    )
    (net (code "37") (name "Net-(U3B-VCAP_2)") (class "Default")
      (node (ref "C13") (pin "1") (pinfunction "1_1") (pintype "passive"))
      (node (ref "U3") (pin "47") (pinfunction "VCAP_2_47") (pintype "power_in"))
    )
    (net (code "38") (name "Net-(U4-OUT)") (class "Default")
      (node (ref "R7") (pin "1") (pinfunction "1_1") (pintype "passive"))
      (node (ref "U4") (pin "6") (pinfunction "OUT_6") (pintype "output"))
    )
    (net (code "39") (name "Net-(U4-REF)") (class "Default")
      (node (ref "C7") (pin "1") (pinfunction "1_1") (pintype "passive"))
      (node (ref "U4") (pin "1") (pinfunction "REF_1") (pintype "input"))
    )
    (net (code "40") (name "Net-(U5-OUT)") (class "Default")
      (node (ref "R10") (pin "1") (pinfunction "1_1") (pintype "passive"))
      (node (ref "U5") (pin "6") (pinfunction "OUT_6") (pintype "output"))
    )
    (net (code "41") (name "Net-(U5-REF)") (class "Default")
      (node (ref "C10") (pin "1") (pinfunction "1_1") (pintype "passive"))
      (node (ref "U5") (pin "1") (pinfunction "REF_1") (pintype "input"))
    )
    (net (code "42") (name "Net-(U6-OUT)") (class "Default")
      (node (ref "R17") (pin "1") (pinfunction "1_1") (pintype "passive"))
      (node (ref "U6") (pin "6") (pinfunction "OUT_6") (pintype "output"))
    )
    (net (code "43") (name "Net-(U6-REF)") (class "Default")
      (node (ref "C22") (pin "1") (pinfunction "1_1") (pintype "passive"))
      (node (ref "U6") (pin "1") (pinfunction "REF_1") (pintype "input"))
    )
    (net (code "44") (name "Net-(Y1-OUT)") (class "Default")
      (node (ref "R1") (pin "2") (pinfunction "2_2") (pintype "passive"))
      (node (ref "Y1") (pin "3") (pinfunction "OUT_3") (pintype "output"))
    )
    (net (code "45") (name "Net-(Y1-VDD)") (class "Default")
      (node (ref "C2") (pin "2") (pinfunction "2_2") (pintype "passive"))
      (node (ref "C3") (pin "2") (pinfunction "2_2") (pintype "passive"))
      (node (ref "R2") (pin "1") (pinfunction "1_1") (pintype "passive"))
      (node (ref "Y1") (pin "4") (pinfunction "VDD_4") (pintype "power_in"))
    )
    (net (code "46") (name "unconnected-(J7-Pad1)") (class "Default")
      (node (ref "J7") (pin "1") (pinfunction "1_1") (pintype "passive+no_connect"))
    )
    (net (code "47") (name "unconnected-(J7-Pad9)") (class "Default")
      (node (ref "J7") (pin "9") (pinfunction "9_9") (pintype "passive+no_connect"))
    )
    (net (code "48") (name "unconnected-(J7-Pad11)") (class "Default")
      (node (ref "J7") (pin "11") (pinfunction "11_11") (pintype "passive+no_connect"))
    )
    (net (code "49") (name "unconnected-(U1-DNC-PadU8)") (class "Default")
      (node (ref "U1") (pin "U8") (pinfunction "DNC_U8") (pintype "passive+no_connect"))
    )
    (net (code "50") (name "unconnected-(U3B-PA0_WKUP-Pad14)") (class "Default")
      (node (ref "U3") (pin "14") (pinfunction "PA0_WKUP_14") (pintype "bidirectional"))
    )
    (net (code "51") (name "unconnected-(U3B-PA1-Pad15)") (class "Default")
      (node (ref "U3") (pin "15") (pinfunction "PA1_15") (pintype "bidirectional"))
    )
    (net (code "52") (name "unconnected-(U3B-PA2-Pad16)") (class "Default")
      (node (ref "U3") (pin "16") (pinfunction "PA2_16") (pintype "bidirectional"))
    )
    (net (code "53") (name "unconnected-(U3B-PA4-Pad20)") (class "Default")
      (node (ref "U3") (pin "20") (pinfunction "PA4_20") (pintype "bidirectional"))
    )
    (net (code "54") (name "unconnected-(U3B-PA5-Pad21)") (class "Default")
      (node (ref "U3") (pin "21") (pinfunction "PA5_21") (pintype "bidirectional"))
    )
    (net (code "55") (name "unconnected-(U3B-PA6-Pad22)") (class "Default")
      (node (ref "U3") (pin "22") (pinfunction "PA6_22") (pintype "bidirectional"))
    )
    (net (code "56") (name "unconnected-(U3B-PA8-Pad41)") (class "Default")
      (node (ref "U3") (pin "41") (pinfunction "PA8_41") (pintype "bidirectional"))
    )
    (net (code "57") (name "unconnected-(U3B-PA9-Pad42)") (class "Default")
      (node (ref "U3") (pin "42") (pinfunction "PA9_42") (pintype "bidirectional"))
    )
    (net (code "58") (name "unconnected-(U3B-PA10-Pad43)") (class "Default")
      (node (ref "U3") (pin "43") (pinfunction "PA10_43") (pintype "bidirectional"))
    )
    (net (code "59") (name "unconnected-(U3B-PA11-Pad44)") (class "Default")
      (node (ref "U3") (pin "44") (pinfunction "PA11_44") (pintype "bidirectional"))
    )
    (net (code "60") (name "unconnected-(U3B-PA12-Pad45)") (class "Default")
      (node (ref "U3") (pin "45") (pinfunction "PA12_45") (pintype "bidirectional"))
    )
    (net (code "61") (name "unconnected-(U3B-PA15-Pad50)") (class "Default")
      (node (ref "U3") (pin "50") (pinfunction "PA15_50") (pintype "bidirectional"))
    )
    (net (code "62") (name "unconnected-(U3B-PB0-Pad26)") (class "Default")
      (node (ref "U3") (pin "26") (pinfunction "PB0_26") (pintype "bidirectional"))
    )
    (net (code "63") (name "unconnected-(U3B-PB2-Pad28)") (class "Default")
      (node (ref "U3") (pin "28") (pinfunction "PB2_28") (pintype "bidirectional"))
    )
    (net (code "64") (name "unconnected-(U3B-PB4-Pad56)") (class "Default")
      (node (ref "U3") (pin "56") (pinfunction "PB4_56") (pintype "bidirectional"))
    )
    (net (code "65") (name "unconnected-(U3B-PB5-Pad57)") (class "Default")
      (node (ref "U3") (pin "57") (pinfunction "PB5_57") (pintype "bidirectional"))
    )
    (net (code "66") (name "unconnected-(U3B-PB8-Pad61)") (class "Default")
      (node (ref "U3") (pin "61") (pinfunction "PB8_61") (pintype "bidirectional"))
    )
    (net (code "67") (name "unconnected-(U3B-PB9-Pad62)") (class "Default")
      (node (ref "U3") (pin "62") (pinfunction "PB9_62") (pintype "bidirectional"))
    )
    (net (code "68") (name "unconnected-(U3B-PB10-Pad29)") (class "Default")
      (node (ref "U3") (pin "29") (pinfunction "PB10_29") (pintype "bidirectional"))
    )
    (net (code "69") (name "unconnected-(U3B-PB11-Pad30)") (class "Default")
      (node (ref "U3") (pin "30") (pinfunction "PB11_30") (pintype "bidirectional"))
    )
    (net (code "70") (name "unconnected-(U3B-PB12-Pad33)") (class "Default")
      (node (ref "U3") (pin "33") (pinfunction "PB12_33") (pintype "bidirectional"))
    )
    (net (code "71") (name "unconnected-(U3B-PC0-Pad8)") (class "Default")
      (node (ref "U3") (pin "8") (pinfunction "PC0_8") (pintype "bidirectional"))
    )
    (net (code "72") (name "unconnected-(U3B-PC1-Pad9)") (class "Default")
      (node (ref "U3") (pin "9") (pinfunction "PC1_9") (pintype "bidirectional"))
    )
    (net (code "73") (name "unconnected-(U3B-PC2-Pad10)") (class "Default")
      (node (ref "U3") (pin "10") (pinfunction "PC2_10") (pintype "bidirectional"))
    )
    (net (code "74") (name "unconnected-(U3B-PC3-Pad11)") (class "Default")
      (node (ref "U3") (pin "11") (pinfunction "PC3_11") (pintype "bidirectional"))
    )
    (net (code "75") (name "unconnected-(U3B-PC4-Pad24)") (class "Default")
      (node (ref "U3") (pin "24") (pinfunction "PC4_24") (pintype "bidirectional"))
    )
    (net (code "76") (name "unconnected-(U3B-PC5-Pad25)") (class "Default")
      (node (ref "U3") (pin "25") (pinfunction "PC5_25") (pintype "bidirectional"))
    )
    (net (code "77") (name "unconnected-(U3B-PC8-Pad39)") (class "Default")
      (node (ref "U3") (pin "39") (pinfunction "PC8_39") (pintype "bidirectional"))
    )
    (net (code "78") (name "unconnected-(U3B-PC9-Pad40)") (class "Default")
      (node (ref "U3") (pin "40") (pinfunction "PC9_40") (pintype "bidirectional"))
    )
    (net (code "79") (name "unconnected-(U3B-PC10-Pad51)") (class "Default")
      (node (ref "U3") (pin "51") (pinfunction "PC10_51") (pintype "bidirectional"))
    )
    (net (code "80") (name "unconnected-(U3B-PC11-Pad52)") (class "Default")
      (node (ref "U3") (pin "52") (pinfunction "PC11_52") (pintype "bidirectional"))
    )
    (net (code "81") (name "unconnected-(U3B-PC12-Pad53)") (class "Default")
      (node (ref "U3") (pin "53") (pinfunction "PC12_53") (pintype "bidirectional"))
    )
    (net (code "82") (name "unconnected-(U3B-PC13-Pad2)") (class "Default")
      (node (ref "U3") (pin "2") (pinfunction "PC13_2") (pintype "bidirectional"))
    )
    (net (code "83") (name "unconnected-(U3B-PC14{slash}OSC32_IN-Pad3)") (class "Default")
      (node (ref "U3") (pin "3") (pinfunction "PC14/OSC32_IN_3") (pintype "bidirectional"))
    )
    (net (code "84") (name "unconnected-(U3B-PC15{slash}OSC32_OUT-Pad4)") (class "Default")
      (node (ref "U3") (pin "4") (pinfunction "PC15/OSC32_OUT_4") (pintype "bidirectional"))
    )
    (net (code "85") (name "unconnected-(U3B-PD2-Pad54)") (class "Default")
      (node (ref "U3") (pin "54") (pinfunction "PD2_54") (pintype "bidirectional"))
    )
    (net (code "86") (name "unconnected-(U3B-PH1{slash}OSC_OUT-Pad6)") (class "Default")
      (node (ref "U3") (pin "6") (pinfunction "PH1/OSC_OUT_6") (pintype "bidirectional+no_connect"))
    )
  )
)
